# header.net
KiCad netlist of a schematic drawn in Altium Designer
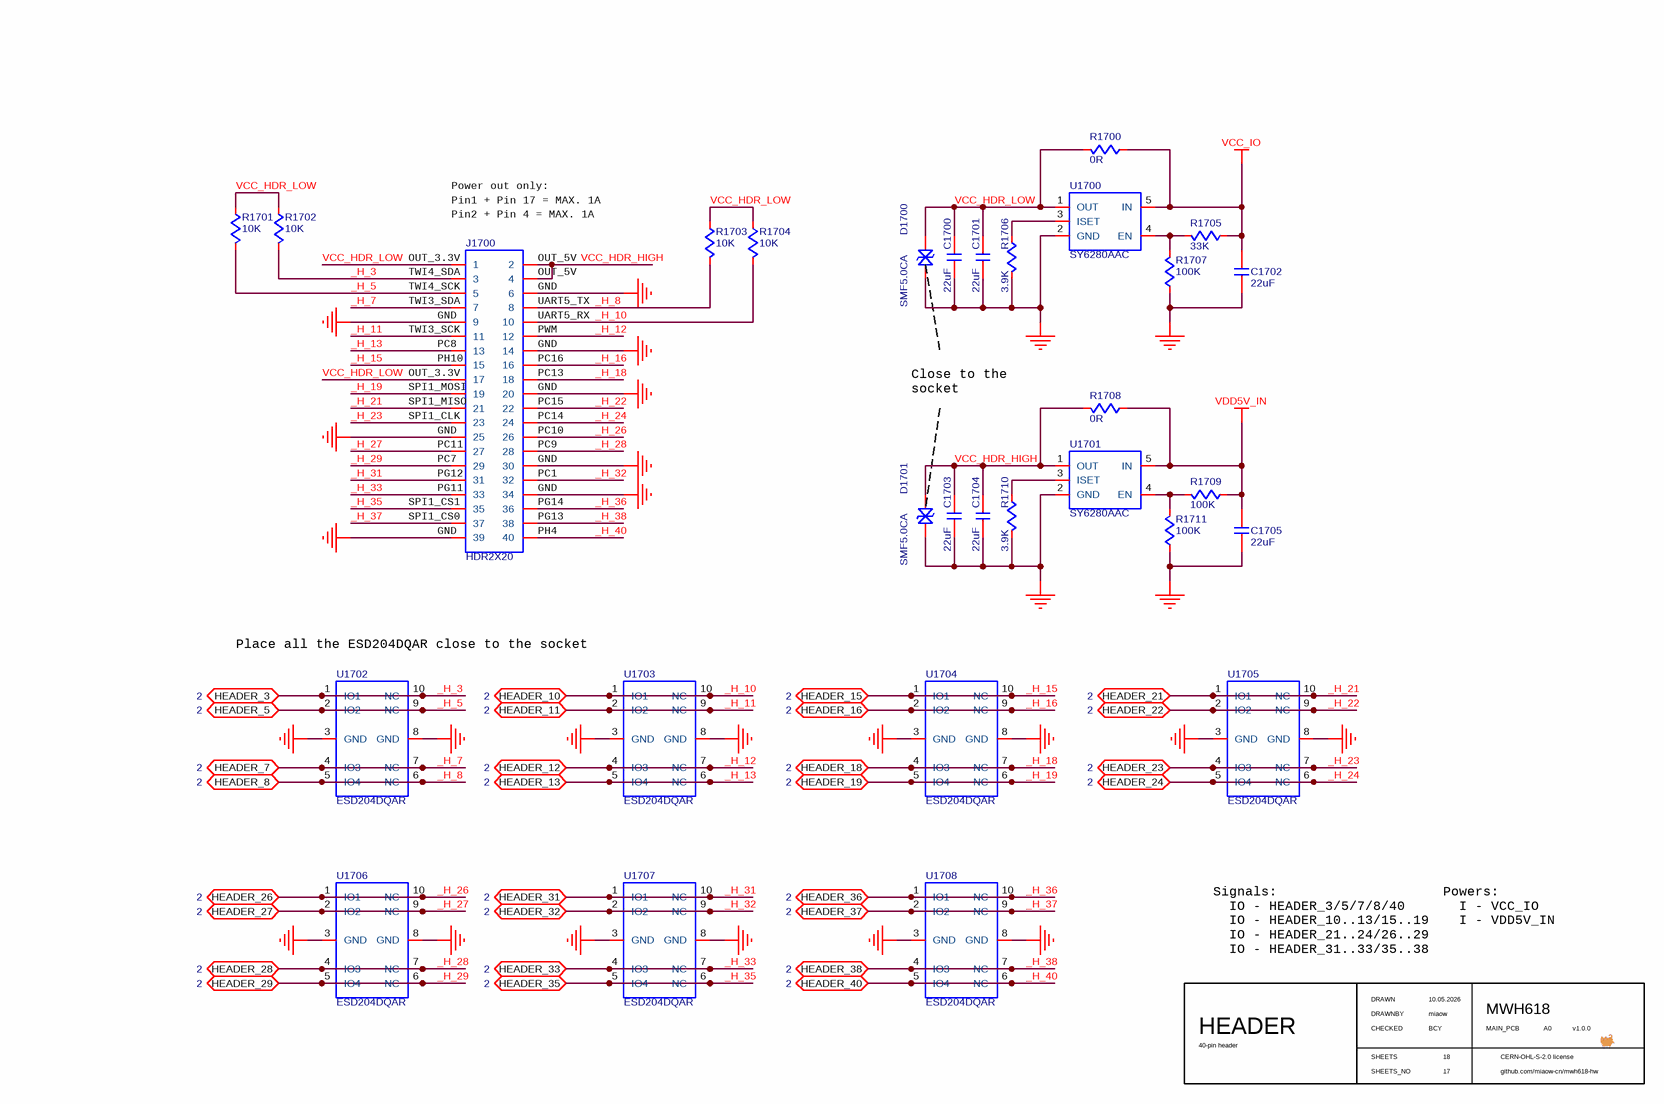
[diagram p0: header.schdoc]

(export (version "E")
  (design (tool "Eeschema 10.0.6"))
  (components
    (comp (ref "C1700")
      (value "22uF")
      (footprint "mw:C0603")
      (fields (field (name "VOLTAGE") "10V") (field (name "Comment") "C-NOMO"))
      (libsource (lib "mw") (part "C-NOMO"))
    )
    (comp (ref "C1701")
      (value "22uF")
      (footprint "mw:C0603")
      (fields (field (name "VOLTAGE") "10V") (field (name "Comment") "C-NOMO"))
      (libsource (lib "mw") (part "C-NOMO"))
    )
    (comp (ref "C1702")
      (value "22uF")
      (footprint "mw:C0603")
      (fields (field (name "VOLTAGE") "10V") (field (name "Comment") "C-NOMO"))
      (libsource (lib "mw") (part "C-NOMO"))
    )
    (comp (ref "C1703")
      (value "22uF")
      (footprint "mw:C0603")
      (fields (field (name "VOLTAGE") "10V") (field (name "Comment") "C-NOMO"))
      (libsource (lib "mw") (part "C-NOMO"))
    )
    (comp (ref "C1704")
      (value "22uF")
      (footprint "mw:C0603")
      (fields (field (name "VOLTAGE") "10V") (field (name "Comment") "C-NOMO"))
      (libsource (lib "mw") (part "C-NOMO"))
    )
    (comp (ref "C1705")
      (value "22uF")
      (footprint "mw:C0603")
      (fields (field (name "VOLTAGE") "10V") (field (name "Comment") "C-NOMO"))
      (libsource (lib "mw") (part "C-NOMO"))
    )
    (comp (ref "D1700")
      (value "SMF5.0CA")
      (footprint "mw:SMF5.0CA")
      (description "TVS/ESD")
      (libsource (lib "mw") (part "SMF5.0CA"))
    )
    (comp (ref "D1701")
      (value "SMF5.0CA")
      (footprint "mw:SMF5.0CA")
      (description "TVS/ESD")
      (libsource (lib "mw") (part "SMF5.0CA"))
    )
    (comp (ref "J1700") (value "HDR2X20") (footprint "mw:HDR2X20") (libsource (lib "mw") (part "HDR2X20")))
    (comp (ref "R1700")
      (value "0R")
      (footprint "mw:R1206")
      (fields (field (name "Comment") "R"))
      (libsource (lib "mw") (part "R"))
    )
    (comp (ref "R1701")
      (value "10K")
      (footprint "mw:R0402")
      (fields (field (name "Comment") "R"))
      (libsource (lib "mw") (part "R"))
    )
    (comp (ref "R1702")
      (value "10K")
      (footprint "mw:R0402")
      (fields (field (name "Comment") "R"))
      (libsource (lib "mw") (part "R"))
    )
    (comp (ref "R1703")
      (value "10K")
      (footprint "mw:R0402")
      (fields (field (name "Comment") "R"))
      (libsource (lib "mw") (part "R"))
    )
    (comp (ref "R1704")
      (value "10K")
      (footprint "mw:R0402")
      (fields (field (name "Comment") "R"))
      (libsource (lib "mw") (part "R"))
    )
    (comp (ref "R1705")
      (value "33K")
      (footprint "mw:R0402")
      (fields (field (name "Comment") "R"))
      (libsource (lib "mw") (part "R"))
    )
    (comp (ref "R1706")
      (value "3.9K")
      (footprint "mw:R0402")
      (fields (field (name "Comment") "R"))
      (libsource (lib "mw") (part "R"))
    )
    (comp (ref "R1707")
      (value "100K")
      (footprint "mw:R0402")
      (fields (field (name "Comment") "R"))
      (libsource (lib "mw") (part "R"))
    )
    (comp (ref "R1708")
      (value "0R")
      (footprint "mw:R1206")
      (fields (field (name "Comment") "R"))
      (libsource (lib "mw") (part "R"))
    )
    (comp (ref "R1709")
      (value "100K")
      (footprint "mw:R0402")
      (fields (field (name "Comment") "R"))
      (libsource (lib "mw") (part "R"))
    )
    (comp (ref "R1710")
      (value "3.9K")
      (footprint "mw:R0402")
      (fields (field (name "Comment") "R"))
      (libsource (lib "mw") (part "R"))
    )
    (comp (ref "R1711")
      (value "100K")
      (footprint "mw:R0402")
      (fields (field (name "Comment") "R"))
      (libsource (lib "mw") (part "R"))
    )
    (comp (ref "U1700")
      (value "SY6280AAC")
      (footprint "mw:SY6280AAC")
      (description "PWR SWITCH")
      (libsource (lib "mw") (part "SY6280AAC"))
    )
    (comp (ref "U1701")
      (value "SY6280AAC")
      (footprint "mw:SY6280AAC")
      (description "PWR SWITCH")
      (libsource (lib "mw") (part "SY6280AAC"))
    )
    (comp (ref "U1702")
      (value "ESD204DQAR")
      (footprint "mw:ESD204DQAR")
      (description "TVS/ESD - 4 ch, 3.6V, 5V, 0.55pF@1MHz, 30KV")
      (libsource (lib "mw") (part "ESD204DQAR"))
    )
    (comp (ref "U1703")
      (value "ESD204DQAR")
      (footprint "mw:ESD204DQAR")
      (description "TVS/ESD - 4 ch, 3.6V, 5V, 0.55pF@1MHz, 30KV")
      (libsource (lib "mw") (part "ESD204DQAR"))
    )
    (comp (ref "U1704")
      (value "ESD204DQAR")
      (footprint "mw:ESD204DQAR")
      (description "TVS/ESD - 4 ch, 3.6V, 5V, 0.55pF@1MHz, 30KV")
      (libsource (lib "mw") (part "ESD204DQAR"))
    )
    (comp (ref "U1705")
      (value "ESD204DQAR")
      (footprint "mw:ESD204DQAR")
      (description "TVS/ESD - 4 ch, 3.6V, 5V, 0.55pF@1MHz, 30KV")
      (libsource (lib "mw") (part "ESD204DQAR"))
    )
    (comp (ref "U1706")
      (value "ESD204DQAR")
      (footprint "mw:ESD204DQAR")
      (description "TVS/ESD - 4 ch, 3.6V, 5V, 0.55pF@1MHz, 30KV")
      (libsource (lib "mw") (part "ESD204DQAR"))
    )
    (comp (ref "U1707")
      (value "ESD204DQAR")
      (footprint "mw:ESD204DQAR")
      (description "TVS/ESD - 4 ch, 3.6V, 5V, 0.55pF@1MHz, 30KV")
      (libsource (lib "mw") (part "ESD204DQAR"))
    )
    (comp (ref "U1708")
      (value "ESD204DQAR")
      (footprint "mw:ESD204DQAR")
      (description "TVS/ESD - 4 ch, 3.6V, 5V, 0.55pF@1MHz, 30KV")
      (libsource (lib "mw") (part "ESD204DQAR"))
    )
  )
  (nets
    (net (code "1") (name "/VCC_HDR_HIGH") (class "Default")
      (node (ref "C1703") (pin "2") (pinfunction "2_2") (pintype "passive"))
      (node (ref "C1704") (pin "2") (pinfunction "2_2") (pintype "passive"))
      (node (ref "D1701") (pin "2") (pinfunction "2_2") (pintype "passive"))
      (node (ref "J1700") (pin "2") (pinfunction "2_2") (pintype "passive"))
      (node (ref "J1700") (pin "4") (pinfunction "4_4") (pintype "passive"))
      (node (ref "R1708") (pin "1") (pinfunction "1_1") (pintype "passive"))
      (node (ref "U1701") (pin "1") (pinfunction "OUT_1") (pintype "passive"))
    )
    (net (code "2") (name "/VCC_HDR_LOW") (class "Default")
      (node (ref "C1700") (pin "2") (pinfunction "2_2") (pintype "passive"))
      (node (ref "C1701") (pin "2") (pinfunction "2_2") (pintype "passive"))
      (node (ref "D1700") (pin "2") (pinfunction "2_2") (pintype "passive"))
      (node (ref "J1700") (pin "1") (pinfunction "1_1") (pintype "passive"))
      (node (ref "J1700") (pin "17") (pinfunction "17_17") (pintype "passive"))
      (node (ref "R1700") (pin "1") (pinfunction "1_1") (pintype "passive"))
      (node (ref "R1701") (pin "2") (pinfunction "2_2") (pintype "passive"))
      (node (ref "R1702") (pin "2") (pinfunction "2_2") (pintype "passive"))
      (node (ref "R1703") (pin "2") (pinfunction "2_2") (pintype "passive"))
      (node (ref "R1704") (pin "2") (pinfunction "2_2") (pintype "passive"))
      (node (ref "U1700") (pin "1") (pinfunction "OUT_1") (pintype "passive"))
    )
    (net (code "3") (name "/_H_3") (class "Default")
      (node (ref "J1700") (pin "3") (pinfunction "3_3") (pintype "passive"))
      (node (ref "R1702") (pin "1") (pinfunction "1_1") (pintype "passive"))
      (node (ref "U1702") (pin "1") (pinfunction "IO1_1") (pintype "passive"))
      (node (ref "U1702") (pin "10") (pinfunction "NC_10") (pintype "passive"))
    )
    (net (code "4") (name "/_H_5") (class "Default")
      (node (ref "J1700") (pin "5") (pinfunction "5_5") (pintype "passive"))
      (node (ref "R1701") (pin "1") (pinfunction "1_1") (pintype "passive"))
      (node (ref "U1702") (pin "2") (pinfunction "IO2_2") (pintype "passive"))
      (node (ref "U1702") (pin "9") (pinfunction "NC_9") (pintype "passive"))
    )
    (net (code "5") (name "/_H_7") (class "Default")
      (node (ref "J1700") (pin "7") (pinfunction "7_7") (pintype "passive"))
      (node (ref "U1702") (pin "4") (pinfunction "IO3_4") (pintype "passive"))
      (node (ref "U1702") (pin "7") (pinfunction "NC_7") (pintype "passive"))
    )
    (net (code "6") (name "/_H_8") (class "Default")
      (node (ref "J1700") (pin "8") (pinfunction "8_8") (pintype "passive"))
      (node (ref "R1703") (pin "1") (pinfunction "1_1") (pintype "passive"))
      (node (ref "U1702") (pin "5") (pinfunction "IO4_5") (pintype "passive"))
      (node (ref "U1702") (pin "6") (pinfunction "NC_6") (pintype "passive"))
    )
    (net (code "7") (name "/_H_10") (class "Default")
      (node (ref "J1700") (pin "10") (pinfunction "10_10") (pintype "passive"))
      (node (ref "R1704") (pin "1") (pinfunction "1_1") (pintype "passive"))
      (node (ref "U1703") (pin "1") (pinfunction "IO1_1") (pintype "passive"))
      (node (ref "U1703") (pin "10") (pinfunction "NC_10") (pintype "passive"))
    )
    (net (code "8") (name "/_H_11") (class "Default")
      (node (ref "J1700") (pin "11") (pinfunction "11_11") (pintype "passive"))
      (node (ref "U1703") (pin "2") (pinfunction "IO2_2") (pintype "passive"))
      (node (ref "U1703") (pin "9") (pinfunction "NC_9") (pintype "passive"))
    )
    (net (code "9") (name "/_H_12") (class "Default")
      (node (ref "J1700") (pin "12") (pinfunction "12_12") (pintype "passive"))
      (node (ref "U1703") (pin "4") (pinfunction "IO3_4") (pintype "passive"))
      (node (ref "U1703") (pin "7") (pinfunction "NC_7") (pintype "passive"))
    )
    (net (code "10") (name "/_H_13") (class "Default")
      (node (ref "J1700") (pin "13") (pinfunction "13_13") (pintype "passive"))
      (node (ref "U1703") (pin "5") (pinfunction "IO4_5") (pintype "passive"))
      (node (ref "U1703") (pin "6") (pinfunction "NC_6") (pintype "passive"))
    )
    (net (code "11") (name "/_H_15") (class "Default")
      (node (ref "J1700") (pin "15") (pinfunction "15_15") (pintype "passive"))
      (node (ref "U1704") (pin "1") (pinfunction "IO1_1") (pintype "passive"))
      (node (ref "U1704") (pin "10") (pinfunction "NC_10") (pintype "passive"))
    )
    (net (code "12") (name "/_H_16") (class "Default")
      (node (ref "J1700") (pin "16") (pinfunction "16_16") (pintype "passive"))
      (node (ref "U1704") (pin "2") (pinfunction "IO2_2") (pintype "passive"))
      (node (ref "U1704") (pin "9") (pinfunction "NC_9") (pintype "passive"))
    )
    (net (code "13") (name "/_H_18") (class "Default")
      (node (ref "J1700") (pin "18") (pinfunction "18_18") (pintype "passive"))
      (node (ref "U1704") (pin "4") (pinfunction "IO3_4") (pintype "passive"))
      (node (ref "U1704") (pin "7") (pinfunction "NC_7") (pintype "passive"))
    )
    (net (code "14") (name "/_H_19") (class "Default")
      (node (ref "J1700") (pin "19") (pinfunction "19_19") (pintype "passive"))
      (node (ref "U1704") (pin "5") (pinfunction "IO4_5") (pintype "passive"))
      (node (ref "U1704") (pin "6") (pinfunction "NC_6") (pintype "passive"))
    )
    (net (code "15") (name "/_H_21") (class "Default")
      (node (ref "J1700") (pin "21") (pinfunction "21_21") (pintype "passive"))
      (node (ref "U1705") (pin "1") (pinfunction "IO1_1") (pintype "passive"))
      (node (ref "U1705") (pin "10") (pinfunction "NC_10") (pintype "passive"))
    )
    (net (code "16") (name "/_H_22") (class "Default")
      (node (ref "J1700") (pin "22") (pinfunction "22_22") (pintype "passive"))
      (node (ref "U1705") (pin "2") (pinfunction "IO2_2") (pintype "passive"))
      (node (ref "U1705") (pin "9") (pinfunction "NC_9") (pintype "passive"))
    )
    (net (code "17") (name "/_H_23") (class "Default")
      (node (ref "J1700") (pin "23") (pinfunction "23_23") (pintype "passive"))
      (node (ref "U1705") (pin "4") (pinfunction "IO3_4") (pintype "passive"))
      (node (ref "U1705") (pin "7") (pinfunction "NC_7") (pintype "passive"))
    )
    (net (code "18") (name "/_H_24") (class "Default")
      (node (ref "J1700") (pin "24") (pinfunction "24_24") (pintype "passive"))
      (node (ref "U1705") (pin "5") (pinfunction "IO4_5") (pintype "passive"))
      (node (ref "U1705") (pin "6") (pinfunction "NC_6") (pintype "passive"))
    )
    (net (code "19") (name "/_H_26") (class "Default")
      (node (ref "J1700") (pin "26") (pinfunction "26_26") (pintype "passive"))
      (node (ref "U1706") (pin "1") (pinfunction "IO1_1") (pintype "passive"))
      (node (ref "U1706") (pin "10") (pinfunction "NC_10") (pintype "passive"))
    )
    (net (code "20") (name "/_H_27") (class "Default")
      (node (ref "J1700") (pin "27") (pinfunction "27_27") (pintype "passive"))
      (node (ref "U1706") (pin "2") (pinfunction "IO2_2") (pintype "passive"))
      (node (ref "U1706") (pin "9") (pinfunction "NC_9") (pintype "passive"))
    )
    (net (code "21") (name "/_H_28") (class "Default")
      (node (ref "J1700") (pin "28") (pinfunction "28_28") (pintype "passive"))
      (node (ref "U1706") (pin "4") (pinfunction "IO3_4") (pintype "passive"))
      (node (ref "U1706") (pin "7") (pinfunction "NC_7") (pintype "passive"))
    )
    (net (code "22") (name "/_H_29") (class "Default")
      (node (ref "J1700") (pin "29") (pinfunction "29_29") (pintype "passive"))
      (node (ref "U1706") (pin "5") (pinfunction "IO4_5") (pintype "passive"))
      (node (ref "U1706") (pin "6") (pinfunction "NC_6") (pintype "passive"))
    )
    (net (code "23") (name "/_H_31") (class "Default")
      (node (ref "J1700") (pin "31") (pinfunction "31_31") (pintype "passive"))
      (node (ref "U1707") (pin "1") (pinfunction "IO1_1") (pintype "passive"))
      (node (ref "U1707") (pin "10") (pinfunction "NC_10") (pintype "passive"))
    )
    (net (code "24") (name "/_H_32") (class "Default")
      (node (ref "J1700") (pin "32") (pinfunction "32_32") (pintype "passive"))
      (node (ref "U1707") (pin "2") (pinfunction "IO2_2") (pintype "passive"))
      (node (ref "U1707") (pin "9") (pinfunction "NC_9") (pintype "passive"))
    )
    (net (code "25") (name "/_H_33") (class "Default")
      (node (ref "J1700") (pin "33") (pinfunction "33_33") (pintype "passive"))
      (node (ref "U1707") (pin "4") (pinfunction "IO3_4") (pintype "passive"))
      (node (ref "U1707") (pin "7") (pinfunction "NC_7") (pintype "passive"))
    )
    (net (code "26") (name "/_H_35") (class "Default")
      (node (ref "J1700") (pin "35") (pinfunction "35_35") (pintype "passive"))
      (node (ref "U1707") (pin "5") (pinfunction "IO4_5") (pintype "passive"))
      (node (ref "U1707") (pin "6") (pinfunction "NC_6") (pintype "passive"))
    )
    (net (code "27") (name "/_H_36") (class "Default")
      (node (ref "J1700") (pin "36") (pinfunction "36_36") (pintype "passive"))
      (node (ref "U1708") (pin "1") (pinfunction "IO1_1") (pintype "passive"))
      (node (ref "U1708") (pin "10") (pinfunction "NC_10") (pintype "passive"))
    )
    (net (code "28") (name "/_H_37") (class "Default")
      (node (ref "J1700") (pin "37") (pinfunction "37_37") (pintype "passive"))
      (node (ref "U1708") (pin "2") (pinfunction "IO2_2") (pintype "passive"))
      (node (ref "U1708") (pin "9") (pinfunction "NC_9") (pintype "passive"))
    )
    (net (code "29") (name "/_H_38") (class "Default")
      (node (ref "J1700") (pin "38") (pinfunction "38_38") (pintype "passive"))
      (node (ref "U1708") (pin "4") (pinfunction "IO3_4") (pintype "passive"))
      (node (ref "U1708") (pin "7") (pinfunction "NC_7") (pintype "passive"))
    )
    (net (code "30") (name "/_H_40") (class "Default")
      (node (ref "J1700") (pin "40") (pinfunction "40_40") (pintype "passive"))
      (node (ref "U1708") (pin "5") (pinfunction "IO4_5") (pintype "passive"))
      (node (ref "U1708") (pin "6") (pinfunction "NC_6") (pintype "passive"))
    )
    (net (code "31") (name "GND") (class "Default")
      (node (ref "C1700") (pin "1") (pinfunction "1_1") (pintype "passive"))
      (node (ref "C1701") (pin "1") (pinfunction "1_1") (pintype "passive"))
      (node (ref "C1702") (pin "2") (pinfunction "2_2") (pintype "passive"))
      (node (ref "C1703") (pin "1") (pinfunction "1_1") (pintype "passive"))
      (node (ref "C1704") (pin "1") (pinfunction "1_1") (pintype "passive"))
      (node (ref "C1705") (pin "1") (pinfunction "1_1") (pintype "passive"))
      (node (ref "D1700") (pin "1") (pinfunction "1_1") (pintype "passive"))
      (node (ref "D1701") (pin "1") (pinfunction "1_1") (pintype "passive"))
      (node (ref "J1700") (pin "14") (pinfunction "14_14") (pintype "passive"))
      (node (ref "J1700") (pin "20") (pinfunction "20_20") (pintype "passive"))
      (node (ref "J1700") (pin "25") (pinfunction "25_25") (pintype "passive"))
      (node (ref "J1700") (pin "30") (pinfunction "30_30") (pintype "passive"))
      (node (ref "J1700") (pin "34") (pinfunction "34_34") (pintype "passive"))
      (node (ref "J1700") (pin "39") (pinfunction "39_39") (pintype "passive"))
      (node (ref "J1700") (pin "6") (pinfunction "6_6") (pintype "passive"))
      (node (ref "J1700") (pin "9") (pinfunction "9_9") (pintype "passive"))
      (node (ref "R1706") (pin "1") (pinfunction "1_1") (pintype "passive"))
      (node (ref "R1707") (pin "2") (pinfunction "2_2") (pintype "passive"))
      (node (ref "R1710") (pin "1") (pinfunction "1_1") (pintype "passive"))
      (node (ref "R1711") (pin "2") (pinfunction "2_2") (pintype "passive"))
      (node (ref "U1700") (pin "2") (pinfunction "GND_2") (pintype "passive"))
      (node (ref "U1701") (pin "2") (pinfunction "GND_2") (pintype "passive"))
      (node (ref "U1702") (pin "3") (pinfunction "GND_3") (pintype "passive"))
      (node (ref "U1702") (pin "8") (pinfunction "GND_8") (pintype "passive"))
      (node (ref "U1703") (pin "3") (pinfunction "GND_3") (pintype "passive"))
      (node (ref "U1703") (pin "8") (pinfunction "GND_8") (pintype "passive"))
      (node (ref "U1704") (pin "3") (pinfunction "GND_3") (pintype "passive"))
      (node (ref "U1704") (pin "8") (pinfunction "GND_8") (pintype "passive"))
      (node (ref "U1705") (pin "3") (pinfunction "GND_3") (pintype "passive"))
      (node (ref "U1705") (pin "8") (pinfunction "GND_8") (pintype "passive"))
      (node (ref "U1706") (pin "3") (pinfunction "GND_3") (pintype "passive"))
      (node (ref "U1706") (pin "8") (pinfunction "GND_8") (pintype "passive"))
      (node (ref "U1707") (pin "3") (pinfunction "GND_3") (pintype "passive"))
      (node (ref "U1707") (pin "8") (pinfunction "GND_8") (pintype "passive"))
      (node (ref "U1708") (pin "3") (pinfunction "GND_3") (pintype "passive"))
      (node (ref "U1708") (pin "8") (pinfunction "GND_8") (pintype "passive"))
    )
    (net (code "32") (name "Net-(U1700-EN)") (class "Default")
      (node (ref "R1705") (pin "1") (pinfunction "1_1") (pintype "passive"))
      (node (ref "R1707") (pin "1") (pinfunction "1_1") (pintype "passive"))
      (node (ref "U1700") (pin "4") (pinfunction "EN_4") (pintype "passive"))
    )
    (net (code "33") (name "Net-(U1700-ISET)") (class "Default")
      (node (ref "R1706") (pin "2") (pinfunction "2_2") (pintype "passive"))
      (node (ref "U1700") (pin "3") (pinfunction "ISET_3") (pintype "passive"))
    )
    (net (code "34") (name "Net-(U1701-EN)") (class "Default")
      (node (ref "R1709") (pin "1") (pinfunction "1_1") (pintype "passive"))
      (node (ref "R1711") (pin "1") (pinfunction "1_1") (pintype "passive"))
      (node (ref "U1701") (pin "4") (pinfunction "EN_4") (pintype "passive"))
    )
    (net (code "35") (name "Net-(U1701-ISET)") (class "Default")
      (node (ref "R1710") (pin "2") (pinfunction "2_2") (pintype "passive"))
      (node (ref "U1701") (pin "3") (pinfunction "ISET_3") (pintype "passive"))
    )
    (net (code "36") (name "VCC_IO") (class "Default")
      (node (ref "C1702") (pin "1") (pinfunction "1_1") (pintype "passive"))
      (node (ref "R1700") (pin "2") (pinfunction "2_2") (pintype "passive"))
      (node (ref "R1705") (pin "2") (pinfunction "2_2") (pintype "passive"))
      (node (ref "U1700") (pin "5") (pinfunction "IN_5") (pintype "passive"))
    )
    (net (code "37") (name "VDD5V_IN") (class "Default")
      (node (ref "C1705") (pin "2") (pinfunction "2_2") (pintype "passive"))
      (node (ref "R1708") (pin "2") (pinfunction "2_2") (pintype "passive"))
      (node (ref "R1709") (pin "2") (pinfunction "2_2") (pintype "passive"))
      (node (ref "U1701") (pin "5") (pinfunction "IN_5") (pintype "passive"))
    )
  )
)
